# analog_channel3.net
KiCad netlist of a schematic drawn in Altium Designer
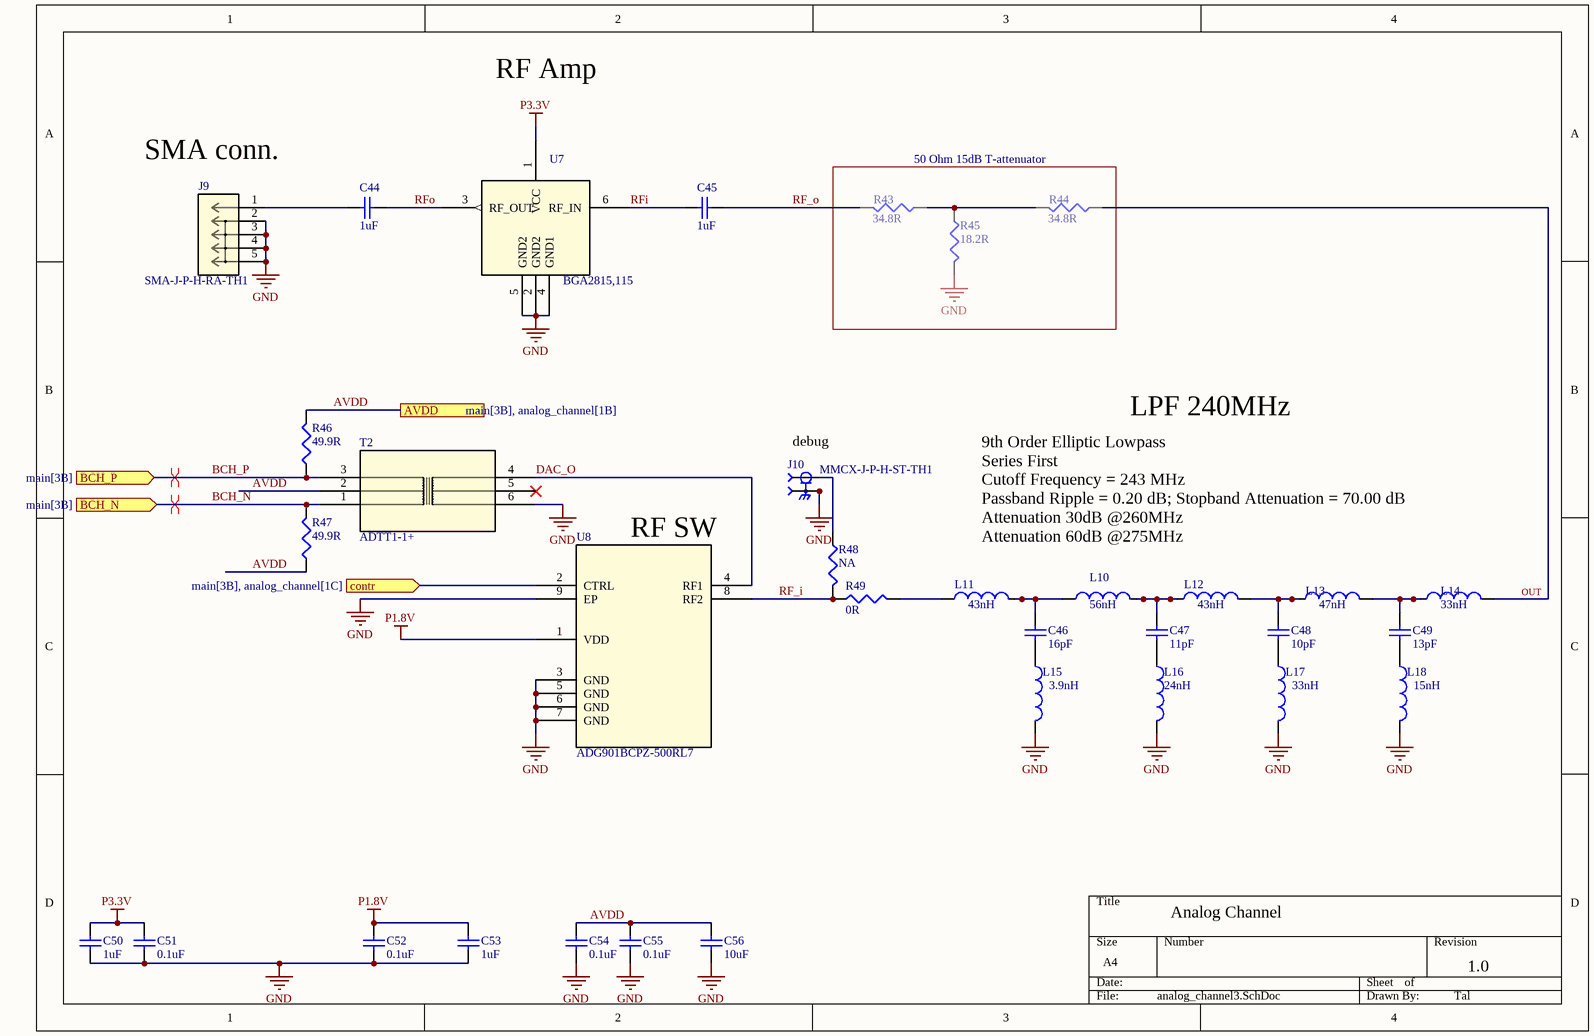
[diagram p0: analog_channel3.SchDoc]

(export (version "E")
  (design (tool "Eeschema 10.0.6"))
  (components
    (comp (ref "C44")
      (value "1uF 25V")
      (footprint "c0402")
      (description "CAP CER 1uF 25V X5R 0402")
      (fields
        (field (name "MANUFACTURER PART NUMBER") "C1005C0G1H6R8D")
        (field (name "MANUFACTURER") "TDK Corporation")
        (field (name "CAPACITANCE") "1uF")
      )
      (libsource (lib "L_SCH_C") (part "CAP CER 6.8pF 50V NP0 0402"))
    )
    (comp (ref "C45")
      (value "1uF 25V")
      (footprint "c0402")
      (description "CAP CER 1uF 25V X5R 0402")
      (fields
        (field (name "MANUFACTURER PART NUMBER") "C1005C0G1H6R8D")
        (field (name "MANUFACTURER") "TDK Corporation")
        (field (name "CAPACITANCE") "1uF")
      )
      (libsource (lib "L_SCH_C") (part "CAP CER 6.8pF 50V NP0 0402"))
    )
    (comp (ref "C46")
      (value "16pF 50V")
      (footprint "c0402")
      (description "CAP CER 16PF 50V 5% NP0 0402")
      (fields
        (field (name "MANUFACTURER") "TDK Corporation")
        (field (name "MANUFACTURER PART NUMBER") "C1005C0G1H200J")
        (field (name "CAPACITANCE") "16pF")
      )
      (libsource (lib "L_SCH_C") (part "CAP CER 20pF 50V 5% NP0 0402"))
    )
    (comp (ref "C47")
      (value "11pF 50V")
      (footprint "c0402")
      (description "CAP CER 11PF 50V 5% NP0 0402")
      (fields
        (field (name "MANUFACTURER") "TDK Corporation")
        (field (name "MANUFACTURER PART NUMBER") "C1005C0G1H200J")
        (field (name "CAPACITANCE") "11pF")
      )
      (libsource (lib "L_SCH_C") (part "CAP CER 20pF 50V 5% NP0 0402"))
    )
    (comp (ref "C48")
      (value "10pF 50V")
      (footprint "c0402")
      (description "CAP CER 10PF 50V 5% NP0 0402")
      (fields
        (field (name "MANUFACTURER") "TDK Corporation")
        (field (name "MANUFACTURER PART NUMBER") "C1005C0G1H200J")
        (field (name "CAPACITANCE") "10pF")
      )
      (libsource (lib "L_SCH_C") (part "CAP CER 20pF 50V 5% NP0 0402"))
    )
    (comp (ref "C49")
      (value "13pF 50V")
      (footprint "c0402")
      (description "CAP CER 13PF 50V 5% NP0 0402")
      (fields
        (field (name "MANUFACTURER") "TDK Corporation")
        (field (name "MANUFACTURER PART NUMBER") "C1005C0G1H200J")
        (field (name "CAPACITANCE") "13pF")
      )
      (libsource (lib "L_SCH_C") (part "CAP CER 20pF 50V 5% NP0 0402"))
    )
    (comp (ref "C50")
      (value "1uF 25V")
      (footprint "c0402")
      (description "CAP CER 1uF 25V X5R 0402")
      (fields
        (field (name "MANUFACTURER PART NUMBER") "C1005C0G1H6R8D")
        (field (name "MANUFACTURER") "TDK Corporation")
        (field (name "CAPACITANCE") "1uF")
      )
      (libsource (lib "L_SCH_C") (part "CAP CER 6.8pF 50V NP0 0402"))
    )
    (comp (ref "C51")
      (value "0.1uF 50V")
      (footprint "c0402")
      (description "CAP CER 0.1uF 50V NP0 0402")
      (fields
        (field (name "MANUFACTURER PART NUMBER") "C1005C0G1H6R8D")
        (field (name "MANUFACTURER") "TDK Corporation")
        (field (name "CAPACITANCE") "0.1uF")
      )
      (libsource (lib "L_SCH_C") (part "CAP CER 6.8pF 50V NP0 0402"))
    )
    (comp (ref "C52")
      (value "0.1uF 50V")
      (footprint "c0402")
      (description "CAP CER 0.1uF 50V NP0 0402")
      (fields
        (field (name "MANUFACTURER PART NUMBER") "C1005C0G1H6R8D")
        (field (name "MANUFACTURER") "TDK Corporation")
        (field (name "CAPACITANCE") "0.1uF")
      )
      (libsource (lib "L_SCH_C") (part "CAP CER 6.8pF 50V NP0 0402"))
    )
    (comp (ref "C53")
      (value "1uF 25V")
      (footprint "c0402")
      (description "CAP CER 1uF 25V X5R 0402")
      (fields
        (field (name "MANUFACTURER PART NUMBER") "C1005C0G1H6R8D")
        (field (name "MANUFACTURER") "TDK Corporation")
        (field (name "CAPACITANCE") "1uF")
      )
      (libsource (lib "L_SCH_C") (part "CAP CER 6.8pF 50V NP0 0402"))
    )
    (comp (ref "C54")
      (value "0.1uF 50V")
      (footprint "c0402")
      (description "CAP CER 0.1uF 50V NP0 0402")
      (fields
        (field (name "MANUFACTURER PART NUMBER") "C1005C0G1H6R8D")
        (field (name "MANUFACTURER") "TDK Corporation")
        (field (name "CAPACITANCE") "0.1uF")
      )
      (libsource (lib "L_SCH_C") (part "CAP CER 6.8pF 50V NP0 0402"))
    )
    (comp (ref "C55")
      (value "0.1uF 50V")
      (footprint "c0402")
      (description "CAP CER 0.1uF 50V NP0 0402")
      (fields
        (field (name "MANUFACTURER PART NUMBER") "C1005C0G1H6R8D")
        (field (name "MANUFACTURER") "TDK Corporation")
        (field (name "CAPACITANCE") "0.1uF")
      )
      (libsource (lib "L_SCH_C") (part "CAP CER 6.8pF 50V NP0 0402"))
    )
    (comp (ref "C56")
      (value "10uF 10V")
      (footprint "c0402")
      (description "CAP CER 10uF 10V X5R 0402")
      (fields
        (field (name "MANUFACTURER PART NUMBER") "C1005C0G1H6R8D")
        (field (name "MANUFACTURER") "TDK Corporation")
        (field (name "CAPACITANCE") "10uF")
      )
      (libsource (lib "L_SCH_C") (part "CAP CER 6.8pF 50V NP0 0402"))
    )
    (comp (ref "J9")
      (value "SMA-J-P-H-RA-TH1")
      (footprint "CONN_SMA-J-P-H-RA-TH1_SAI")
      (description "No Description Available")
      (fields (field (name "COPYRIGHT") "Copyright (C) 2023 Ultra Librarian. All rights reserved."))
      (libsource (lib "SMA-J-P-H-RA-TH1") (part "SMA-J-P-H-RA-TH1"))
    )
    (comp (ref "J10")
      (value "MMCX-J-P-H-ST-TH1")
      (footprint "SAMTEC_MMCX-J-P-H-ST-TH1")
      (description "MMCX STRAIGHT, THROUGH HOLE JACK- 50 OHM")
      (fields (field (name "MF") "Samtec"))
      (libsource (lib "MMCX-J-P-H-ST-TH1") (part "MMCX-J-P-H-ST-TH1"))
    )
    (comp (ref "L10")
      (value "56nH")
      (footprint "0402-A")
      (description "Inductor")
      (fields (field (name "PUBLISHER") "Altium Limited"))
      (libsource (lib "Miscellaneous Devices") (part "Inductor"))
    )
    (comp (ref "L11")
      (value "43nH")
      (footprint "0402-A")
      (description "Inductor")
      (fields (field (name "PUBLISHER") "Altium Limited"))
      (libsource (lib "Miscellaneous Devices") (part "Inductor"))
    )
    (comp (ref "L12")
      (value "43nH")
      (footprint "0402-A")
      (description "Inductor")
      (fields (field (name "PUBLISHER") "Altium Limited"))
      (libsource (lib "Miscellaneous Devices") (part "Inductor"))
    )
    (comp (ref "L13")
      (value "47nH")
      (footprint "0402-A")
      (description "Inductor")
      (fields (field (name "PUBLISHER") "Altium Limited"))
      (libsource (lib "Miscellaneous Devices") (part "Inductor"))
    )
    (comp (ref "L14")
      (value "33nH")
      (footprint "0402-A")
      (description "Inductor")
      (fields (field (name "PUBLISHER") "Altium Limited"))
      (libsource (lib "Miscellaneous Devices") (part "Inductor"))
    )
    (comp (ref "L15")
      (value "3.9nH")
      (footprint "0402-A")
      (description "Inductor")
      (fields (field (name "PUBLISHER") "Altium Limited"))
      (libsource (lib "Miscellaneous Devices") (part "Inductor"))
    )
    (comp (ref "L16")
      (value "24nH")
      (footprint "0402-A")
      (description "Inductor")
      (fields (field (name "PUBLISHER") "Altium Limited"))
      (libsource (lib "Miscellaneous Devices") (part "Inductor"))
    )
    (comp (ref "L17")
      (value "33nH")
      (footprint "0402-A")
      (description "Inductor")
      (fields (field (name "PUBLISHER") "Altium Limited"))
      (libsource (lib "Miscellaneous Devices") (part "Inductor"))
    )
    (comp (ref "L18")
      (value "15nH")
      (footprint "0402-A")
      (description "Inductor")
      (fields (field (name "PUBLISHER") "Altium Limited"))
      (libsource (lib "Miscellaneous Devices") (part "Inductor"))
    )
    (comp (ref "R43")
      (value "34.8R")
      (footprint "r0402")
      (description "RES 34.8 OHM 1/10W 1% 0402 SMD")
      (fields
        (field (name "MANUFACTURER PART NUMBER") "ERJ-2RKF1000X")
        (field (name "MANUFACTURER") "Panasonic Electronic Components")
      )
      (libsource (lib "L_SCH_R") (part "RES 100 OHM 1/10W 1% 0402 SMD"))
    )
    (comp (ref "R44")
      (value "34.8R")
      (footprint "r0402")
      (description "RES 34.8 OHM 1/10W 1% 0402 SMD")
      (fields
        (field (name "MANUFACTURER PART NUMBER") "ERJ-2RKF1000X")
        (field (name "MANUFACTURER") "Panasonic Electronic Components")
      )
      (libsource (lib "L_SCH_R") (part "RES 100 OHM 1/10W 1% 0402 SMD"))
    )
    (comp (ref "R45")
      (value "18.2R")
      (footprint "r0402")
      (description "RES 18.2 OHM 1/10W 1% 0402 SMD")
      (fields
        (field (name "MANUFACTURER PART NUMBER") "ERJ-2RKF1000X")
        (field (name "MANUFACTURER") "Panasonic Electronic Components")
      )
      (libsource (lib "L_SCH_R") (part "RES 100 OHM 1/10W 1% 0402 SMD"))
    )
    (comp (ref "R46")
      (value "49.9R")
      (footprint "r0402")
      (description "RES 49.9 OHM 1/10W 1% 0402 SMD")
      (fields
        (field (name "MANUFACTURER PART NUMBER") "ERJ-2RKF1000X")
        (field (name "MANUFACTURER") "Panasonic Electronic Components")
      )
      (libsource (lib "L_SCH_R") (part "RES 100 OHM 1/10W 1% 0402 SMD"))
    )
    (comp (ref "R47")
      (value "49.9R")
      (footprint "r0402")
      (description "RES 49.9 OHM 1/10W 1% 0402 SMD")
      (fields
        (field (name "MANUFACTURER PART NUMBER") "ERJ-2RKF1000X")
        (field (name "MANUFACTURER") "Panasonic Electronic Components")
      )
      (libsource (lib "L_SCH_R") (part "RES 100 OHM 1/10W 1% 0402 SMD"))
    )
    (comp (ref "R48")
      (value "NA")
      (footprint "r0402")
      (description "RES 0 OHM 1/10W 1% 0402 SMD")
      (fields
        (field (name "MANUFACTURER PART NUMBER") "ERJ-2RKF1000X")
        (field (name "MANUFACTURER") "Panasonic Electronic Components")
      )
      (libsource (lib "L_SCH_R") (part "RES 100 OHM 1/10W 1% 0402 SMD"))
    )
    (comp (ref "R49")
      (value "0R")
      (footprint "r0402")
      (description "RES 0 OHM 1/10W 1% 0402 SMD")
      (fields
        (field (name "MANUFACTURER PART NUMBER") "ERJ-2RKF1000X")
        (field (name "MANUFACTURER") "Panasonic Electronic Components")
      )
      (libsource (lib "L_SCH_R") (part "RES 100 OHM 1/10W 1% 0402 SMD"))
    )
    (comp (ref "T2")
      (value "ADTT1-1+")
      (footprint "CD542_MNC")
      (description "No Description Available")
      (fields (field (name "COPYRIGHT") "Copyright (C) 2023 Ultra Librarian. All rights reserved."))
      (libsource (lib "ADTT1-1&plus_") (part "ADTT1-1+"))
    )
    (comp (ref "U7")
      (value "BGA2815,115")
      (footprint "SOT_2815,115_NXP")
      (description "No Description Available")
      (fields (field (name "COPYRIGHT") "Copyright (C) 2023 Ultra Librarian. All rights reserved."))
      (libsource (lib "BGA2815,115") (part "BGA2815,115"))
    )
    (comp (ref "U8")
      (value "ADG901BCPZ-500RL7")
      (footprint "CP_8_2_ADI")
      (description "No Description Available")
      (fields (field (name "COPYRIGHT") "Copyright (C) 2023 Ultra Librarian. All rights reserved."))
      (libsource (lib "ADG901BCPZ-500RL7") (part "ADG901BCPZ-500RL7"))
    )
  )
  (nets
    (net (code "1") (name "/AVDD") (class "Default")
      (node (ref "C54") (pin "2") (pinfunction "2_2") (pintype "passive"))
      (node (ref "C55") (pin "2") (pinfunction "2_2") (pintype "passive"))
      (node (ref "C56") (pin "2") (pinfunction "2_2") (pintype "passive"))
      (node (ref "R46") (pin "2") (pinfunction "2_2") (pintype "passive"))
      (node (ref "R47") (pin "1") (pinfunction "1_1") (pintype "passive"))
      (node (ref "T2") (pin "2") (pinfunction "2_2") (pintype "passive"))
    )
    (net (code "2") (name "/BCH_N") (class "Default")
      (node (ref "R47") (pin "2") (pinfunction "2_2") (pintype "passive"))
      (node (ref "T2") (pin "1") (pinfunction "1_1") (pintype "passive"))
    )
    (net (code "3") (name "/BCH_P") (class "Default")
      (node (ref "R46") (pin "1") (pinfunction "1_1") (pintype "passive"))
      (node (ref "T2") (pin "3") (pinfunction "3_3") (pintype "passive"))
    )
    (net (code "4") (name "/DAC_O") (class "Default")
      (node (ref "T2") (pin "4") (pinfunction "4_4") (pintype "passive"))
      (node (ref "U8") (pin "4") (pinfunction "RF1_4") (pintype "passive"))
    )
    (net (code "5") (name "/OUT") (class "Default")
      (node (ref "L14") (pin "2") (pinfunction "2_2") (pintype "passive"))
      (node (ref "R44") (pin "1") (pinfunction "1_1") (pintype "passive"))
    )
    (net (code "6") (name "/RF_i") (class "Default")
      (node (ref "R48") (pin "2") (pinfunction "2_2") (pintype "passive"))
      (node (ref "R49") (pin "1") (pinfunction "1_1") (pintype "passive"))
      (node (ref "U8") (pin "8") (pinfunction "RF2_8") (pintype "passive"))
    )
    (net (code "7") (name "/RF_o") (class "Default")
      (node (ref "C45") (pin "2") (pinfunction "2_2") (pintype "passive"))
      (node (ref "R43") (pin "2") (pinfunction "2_2") (pintype "passive"))
    )
    (net (code "8") (name "/RFi") (class "Default")
      (node (ref "C45") (pin "1") (pinfunction "1_1") (pintype "passive"))
      (node (ref "U7") (pin "6") (pinfunction "RF_IN_6") (pintype "passive"))
    )
    (net (code "9") (name "/RFo") (class "Default")
      (node (ref "C44") (pin "2") (pinfunction "2_2") (pintype "passive"))
      (node (ref "U7") (pin "3") (pinfunction "RF_OUT_3") (pintype "output"))
    )
    (net (code "10") (name "/contr") (class "Default")
      (node (ref "U8") (pin "2") (pinfunction "CTRL_2") (pintype "passive"))
    )
    (net (code "11") (name "GND") (class "Default")
      (node (ref "C50") (pin "1") (pinfunction "1_1") (pintype "passive"))
      (node (ref "C51") (pin "1") (pinfunction "1_1") (pintype "passive"))
      (node (ref "C52") (pin "1") (pinfunction "1_1") (pintype "passive"))
      (node (ref "C53") (pin "1") (pinfunction "1_1") (pintype "passive"))
      (node (ref "C54") (pin "1") (pinfunction "1_1") (pintype "passive"))
      (node (ref "C55") (pin "1") (pinfunction "1_1") (pintype "passive"))
      (node (ref "C56") (pin "1") (pinfunction "1_1") (pintype "passive"))
      (node (ref "J10") (pin "S1") (pinfunction "2_S1") (pintype "passive"))
      (node (ref "J10") (pin "S2") (pinfunction "2_S2") (pintype "passive"))
      (node (ref "J10") (pin "S3") (pinfunction "2_S3") (pintype "passive"))
      (node (ref "J10") (pin "S4") (pinfunction "2_S4") (pintype "passive"))
      (node (ref "J9") (pin "2") (pinfunction "2_2") (pintype "passive"))
      (node (ref "J9") (pin "3") (pinfunction "3_3") (pintype "passive"))
      (node (ref "J9") (pin "4") (pinfunction "4_4") (pintype "passive"))
      (node (ref "J9") (pin "5") (pinfunction "5_5") (pintype "passive"))
      (node (ref "L15") (pin "2") (pinfunction "2_2") (pintype "passive"))
      (node (ref "L16") (pin "2") (pinfunction "2_2") (pintype "passive"))
      (node (ref "L17") (pin "2") (pinfunction "2_2") (pintype "passive"))
      (node (ref "L18") (pin "2") (pinfunction "2_2") (pintype "passive"))
      (node (ref "R45") (pin "2") (pinfunction "2_2") (pintype "passive"))
      (node (ref "T2") (pin "6") (pinfunction "6_6") (pintype "passive"))
      (node (ref "U7") (pin "2") (pinfunction "GND2_2") (pintype "passive"))
      (node (ref "U7") (pin "4") (pinfunction "GND1_4") (pintype "passive"))
      (node (ref "U7") (pin "5") (pinfunction "GND2_5") (pintype "passive"))
      (node (ref "U8") (pin "3") (pinfunction "GND_3") (pintype "passive"))
      (node (ref "U8") (pin "5") (pinfunction "GND_5") (pintype "passive"))
      (node (ref "U8") (pin "6") (pinfunction "GND_6") (pintype "passive"))
      (node (ref "U8") (pin "7") (pinfunction "GND_7") (pintype "passive"))
      (node (ref "U8") (pin "9") (pinfunction "EP_9") (pintype "passive"))
    )
    (net (code "12") (name "Net-(C44-Pad1)") (class "Default")
      (node (ref "C44") (pin "1") (pinfunction "1_1") (pintype "passive"))
      (node (ref "J9") (pin "1") (pinfunction "1_1") (pintype "passive"))
    )
    (net (code "13") (name "Net-(C46-Pad1)") (class "Default")
      (node (ref "C46") (pin "1") (pinfunction "1_1") (pintype "passive"))
      (node (ref "L10") (pin "1") (pinfunction "1_1") (pintype "passive"))
      (node (ref "L11") (pin "2") (pinfunction "2_2") (pintype "passive"))
    )
    (net (code "14") (name "Net-(C46-Pad2)") (class "Default")
      (node (ref "C46") (pin "2") (pinfunction "2_2") (pintype "passive"))
      (node (ref "L15") (pin "1") (pinfunction "1_1") (pintype "passive"))
    )
    (net (code "15") (name "Net-(C47-Pad1)") (class "Default")
      (node (ref "C47") (pin "1") (pinfunction "1_1") (pintype "passive"))
      (node (ref "L10") (pin "2") (pinfunction "2_2") (pintype "passive"))
      (node (ref "L12") (pin "1") (pinfunction "1_1") (pintype "passive"))
    )
    (net (code "16") (name "Net-(C47-Pad2)") (class "Default")
      (node (ref "C47") (pin "2") (pinfunction "2_2") (pintype "passive"))
      (node (ref "L16") (pin "1") (pinfunction "1_1") (pintype "passive"))
    )
    (net (code "17") (name "Net-(C48-Pad1)") (class "Default")
      (node (ref "C48") (pin "1") (pinfunction "1_1") (pintype "passive"))
      (node (ref "L12") (pin "2") (pinfunction "2_2") (pintype "passive"))
      (node (ref "L13") (pin "1") (pinfunction "1_1") (pintype "passive"))
    )
    (net (code "18") (name "Net-(C48-Pad2)") (class "Default")
      (node (ref "C48") (pin "2") (pinfunction "2_2") (pintype "passive"))
      (node (ref "L17") (pin "1") (pinfunction "1_1") (pintype "passive"))
    )
    (net (code "19") (name "Net-(C49-Pad1)") (class "Default")
      (node (ref "C49") (pin "1") (pinfunction "1_1") (pintype "passive"))
      (node (ref "L13") (pin "2") (pinfunction "2_2") (pintype "passive"))
      (node (ref "L14") (pin "1") (pinfunction "1_1") (pintype "passive"))
    )
    (net (code "20") (name "Net-(C49-Pad2)") (class "Default")
      (node (ref "C49") (pin "2") (pinfunction "2_2") (pintype "passive"))
      (node (ref "L18") (pin "1") (pinfunction "1_1") (pintype "passive"))
    )
    (net (code "21") (name "Net-(J10-Pad1)") (class "Default")
      (node (ref "J10") (pin "1") (pinfunction "1_1") (pintype "passive"))
      (node (ref "R48") (pin "1") (pinfunction "1_1") (pintype "passive"))
    )
    (net (code "22") (name "Net-(L11-Pad1)") (class "Default")
      (node (ref "L11") (pin "1") (pinfunction "1_1") (pintype "passive"))
      (node (ref "R49") (pin "2") (pinfunction "2_2") (pintype "passive"))
    )
    (net (code "23") (name "Net-(R43-Pad1)") (class "Default")
      (node (ref "R43") (pin "1") (pinfunction "1_1") (pintype "passive"))
      (node (ref "R44") (pin "2") (pinfunction "2_2") (pintype "passive"))
      (node (ref "R45") (pin "1") (pinfunction "1_1") (pintype "passive"))
    )
    (net (code "24") (name "P1.8V") (class "Default")
      (node (ref "C52") (pin "2") (pinfunction "2_2") (pintype "passive"))
      (node (ref "C53") (pin "2") (pinfunction "2_2") (pintype "passive"))
      (node (ref "U8") (pin "1") (pinfunction "VDD_1") (pintype "power_in"))
    )
    (net (code "25") (name "P3.3V") (class "Default")
      (node (ref "C50") (pin "2") (pinfunction "2_2") (pintype "passive"))
      (node (ref "C51") (pin "2") (pinfunction "2_2") (pintype "passive"))
      (node (ref "U7") (pin "1") (pinfunction "VCC_1") (pintype "power_in"))
    )
    (net (code "26") (name "unconnected-(T2-Pad5)") (class "Default")
      (node (ref "T2") (pin "5") (pinfunction "5_5") (pintype "passive+no_connect"))
    )
  )
)
